# PGA.net
KiCad netlist of a schematic drawn in Altium Designer
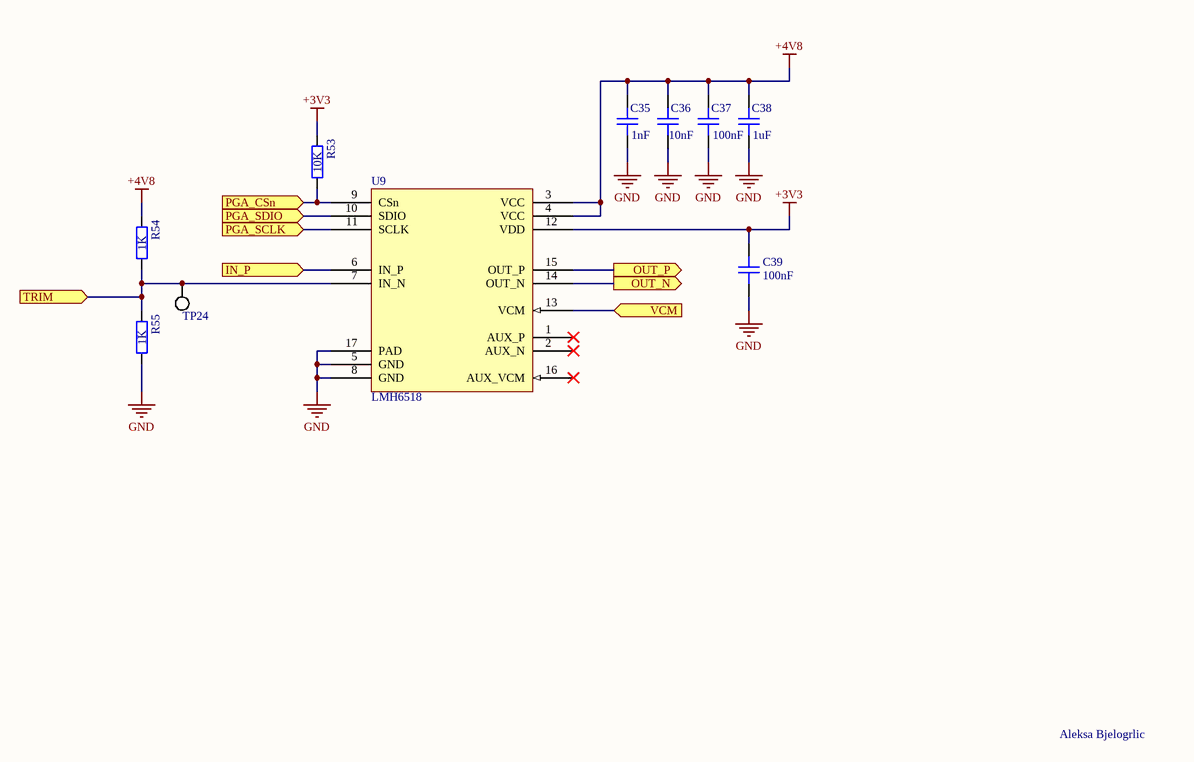
[diagram p0: PGA.SchDoc]

(export (version "E")
  (design (tool "Eeschema 10.0.6"))
  (components
    (comp (ref "C35")
      (value "1nF")
      (footprint "GEN_C_0402")
      (libsource (lib "DSO") (part "CAP 1nF 50V C0G 0402"))
    )
    (comp (ref "C36")
      (value "10nF")
      (footprint "GEN_C_0402")
      (libsource (lib "DSO") (part "CAP 10nF 50V X7R 0402"))
    )
    (comp (ref "C37")
      (value "100nF")
      (footprint "GEN_C_0402")
      (libsource (lib "DSO") (part "CAP 100nF 16V X7R 0402"))
    )
    (comp (ref "C38")
      (value "1uF")
      (footprint "GEN_C_0402")
      (libsource (lib "DSO") (part "CAP 1uF 25V X5R 0402"))
    )
    (comp (ref "C39")
      (value "100nF")
      (footprint "GEN_C_0402")
      (libsource (lib "DSO") (part "CAP 100nF 16V X7R 0402"))
    )
    (comp (ref "R53")
      (value "10K")
      (footprint "GEN_R_0402")
      (fields (field (name "TOLERANCE") "1%"))
      (libsource (lib "DSO") (part "RES 10K OHM 1% 1/10W 0402"))
    )
    (comp (ref "R54")
      (value "1K")
      (footprint "GEN_R_0402")
      (fields (field (name "TOLERANCE") "1%"))
      (libsource (lib "DSO") (part "RES 1K OHM 1% 1/10W 0402"))
    )
    (comp (ref "R55")
      (value "1K")
      (footprint "GEN_R_0402")
      (fields (field (name "TOLERANCE") "1%"))
      (libsource (lib "DSO") (part "RES 1K OHM 1% 1/10W 0402"))
    )
    (comp (ref "TP24") (value "PCB") (footprint "GEN_TP_PCB") (libsource (lib "DSO") (part "TP PCB 1mm")))
    (comp (ref "U9")
      (value "LMH6518")
      (footprint "TI_WQFN_RGH0016A")
      (libsource (lib "DSO") (part "IC PGA LMH6518"))
    )
  )
  (nets
    (net (code "1") (name "+3V3") (class "Default")
      (node (ref "C39") (pin "2") (pinfunction "2_2") (pintype "passive"))
      (node (ref "R53") (pin "2") (pinfunction "2_2") (pintype "passive"))
      (node (ref "U9") (pin "12") (pinfunction "VDD_12") (pintype "power_in"))
    )
    (net (code "2") (name "+4V8") (class "Default")
      (node (ref "C35") (pin "2") (pinfunction "2_2") (pintype "passive"))
      (node (ref "C36") (pin "2") (pinfunction "2_2") (pintype "passive"))
      (node (ref "C37") (pin "2") (pinfunction "2_2") (pintype "passive"))
      (node (ref "C38") (pin "2") (pinfunction "2_2") (pintype "passive"))
      (node (ref "R54") (pin "2") (pinfunction "2_2") (pintype "passive"))
      (node (ref "U9") (pin "3") (pinfunction "VCC_3") (pintype "power_in"))
      (node (ref "U9") (pin "4") (pinfunction "VCC_4") (pintype "power_in"))
    )
    (net (code "3") (name "/IN_P") (class "Default")
      (node (ref "U9") (pin "6") (pinfunction "IN_P_6") (pintype "passive"))
    )
    (net (code "4") (name "/OUT_N") (class "Default")
      (node (ref "U9") (pin "14") (pinfunction "OUT_N_14") (pintype "passive"))
    )
    (net (code "5") (name "/OUT_P") (class "Default")
      (node (ref "U9") (pin "15") (pinfunction "OUT_P_15") (pintype "passive"))
    )
    (net (code "6") (name "/PGA_CSn") (class "Default")
      (node (ref "R53") (pin "1") (pinfunction "1_1") (pintype "passive"))
      (node (ref "U9") (pin "9") (pinfunction "CSn_9") (pintype "passive"))
    )
    (net (code "7") (name "/PGA_SCLK") (class "Default")
      (node (ref "U9") (pin "11") (pinfunction "SCLK_11") (pintype "passive"))
    )
    (net (code "8") (name "/PGA_SDIO") (class "Default")
      (node (ref "U9") (pin "10") (pinfunction "SDIO_10") (pintype "passive"))
    )
    (net (code "9") (name "/TRIM") (class "Default")
      (node (ref "R54") (pin "1") (pinfunction "1_1") (pintype "passive"))
      (node (ref "R55") (pin "2") (pinfunction "2_2") (pintype "passive"))
      (node (ref "TP24") (pin "1") (pinfunction "1_1") (pintype "passive"))
      (node (ref "U9") (pin "7") (pinfunction "IN_N_7") (pintype "passive"))
    )
    (net (code "10") (name "/VCM") (class "Default")
      (node (ref "U9") (pin "13") (pinfunction "VCM_13") (pintype "input"))
    )
    (net (code "11") (name "GND") (class "Default")
      (node (ref "C35") (pin "1") (pinfunction "1_1") (pintype "passive"))
      (node (ref "C36") (pin "1") (pinfunction "1_1") (pintype "passive"))
      (node (ref "C37") (pin "1") (pinfunction "1_1") (pintype "passive"))
      (node (ref "C38") (pin "1") (pinfunction "1_1") (pintype "passive"))
      (node (ref "C39") (pin "1") (pinfunction "1_1") (pintype "passive"))
      (node (ref "R55") (pin "1") (pinfunction "1_1") (pintype "passive"))
      (node (ref "U9") (pin "17") (pinfunction "PAD_17") (pintype "power_in"))
      (node (ref "U9") (pin "5") (pinfunction "GND_5") (pintype "power_in"))
      (node (ref "U9") (pin "8") (pinfunction "GND_8") (pintype "power_in"))
    )
    (net (code "12") (name "unconnected-(U9-AUX_N-Pad2)") (class "Default")
      (node (ref "U9") (pin "2") (pinfunction "AUX_N_2") (pintype "passive+no_connect"))
    )
    (net (code "13") (name "unconnected-(U9-AUX_P-Pad1)") (class "Default")
      (node (ref "U9") (pin "1") (pinfunction "AUX_P_1") (pintype "passive+no_connect"))
    )
    (net (code "14") (name "unconnected-(U9-AUX_VCM-Pad16)") (class "Default")
      (node (ref "U9") (pin "16") (pinfunction "AUX_VCM_16") (pintype "input+no_connect"))
    )
  )
)
